# v1_0.net
KiCad netlist of a schematic drawn in Altium Designer
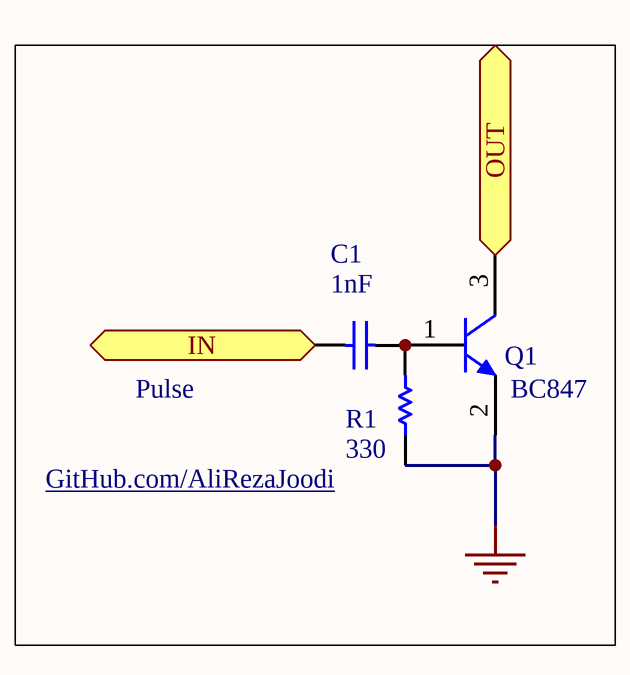
[diagram p0: v1.0.SchDoc]

(export (version "E")
  (design (tool "Eeschema 10.0.6"))
  (components
    (comp (ref "C1")
      (value "1nF")
      (footprint "RESC3216N")
      (description "Capacitor")
      (fields (field (name "Comment") "Cap") (field (name "PUBLISHER") "Altium Limited"))
      (libsource (lib "Miscellaneous Devices") (part "Cap"))
    )
    (comp (ref "Q1")
      (value "BC847")
      (footprint "SOT23-3N")
      (description "Silicon Bipolar Transistor")
      (fields (field (name "Comment") "NPN"))
      (libsource (lib "my Libraries") (part "BC847"))
    )
    (comp (ref "R1")
      (value "330")
      (footprint "0805")
      (description "Resistor")
      (fields (field (name "Comment") "Res1") (field (name "PUBLISHER") "Altium Limited"))
      (libsource (lib "Miscellaneous Devices") (part "Res1"))
    )
  )
  (nets
    (net (code "1") (name "/IN") (class "Default")
      (node (ref "C1") (pin "1") (pinfunction "1_1") (pintype "passive"))
    )
    (net (code "2") (name "/OUT") (class "Default")
      (node (ref "Q1") (pin "3") (pinfunction "C_3") (pintype "passive"))
    )
    (net (code "3") (name "GND") (class "Default")
      (node (ref "Q1") (pin "2") (pinfunction "E_2") (pintype "passive"))
      (node (ref "R1") (pin "1") (pinfunction "1_1") (pintype "passive"))
    )
    (net (code "4") (name "Net-(Q1-B)") (class "Default")
      (node (ref "C1") (pin "2") (pinfunction "2_2") (pintype "passive"))
      (node (ref "Q1") (pin "1") (pinfunction "B_1") (pintype "passive"))
      (node (ref "R1") (pin "2") (pinfunction "2_2") (pintype "passive"))
    )
  )
)
